# CM6206.net
KiCad netlist of a schematic drawn in Altium Designer
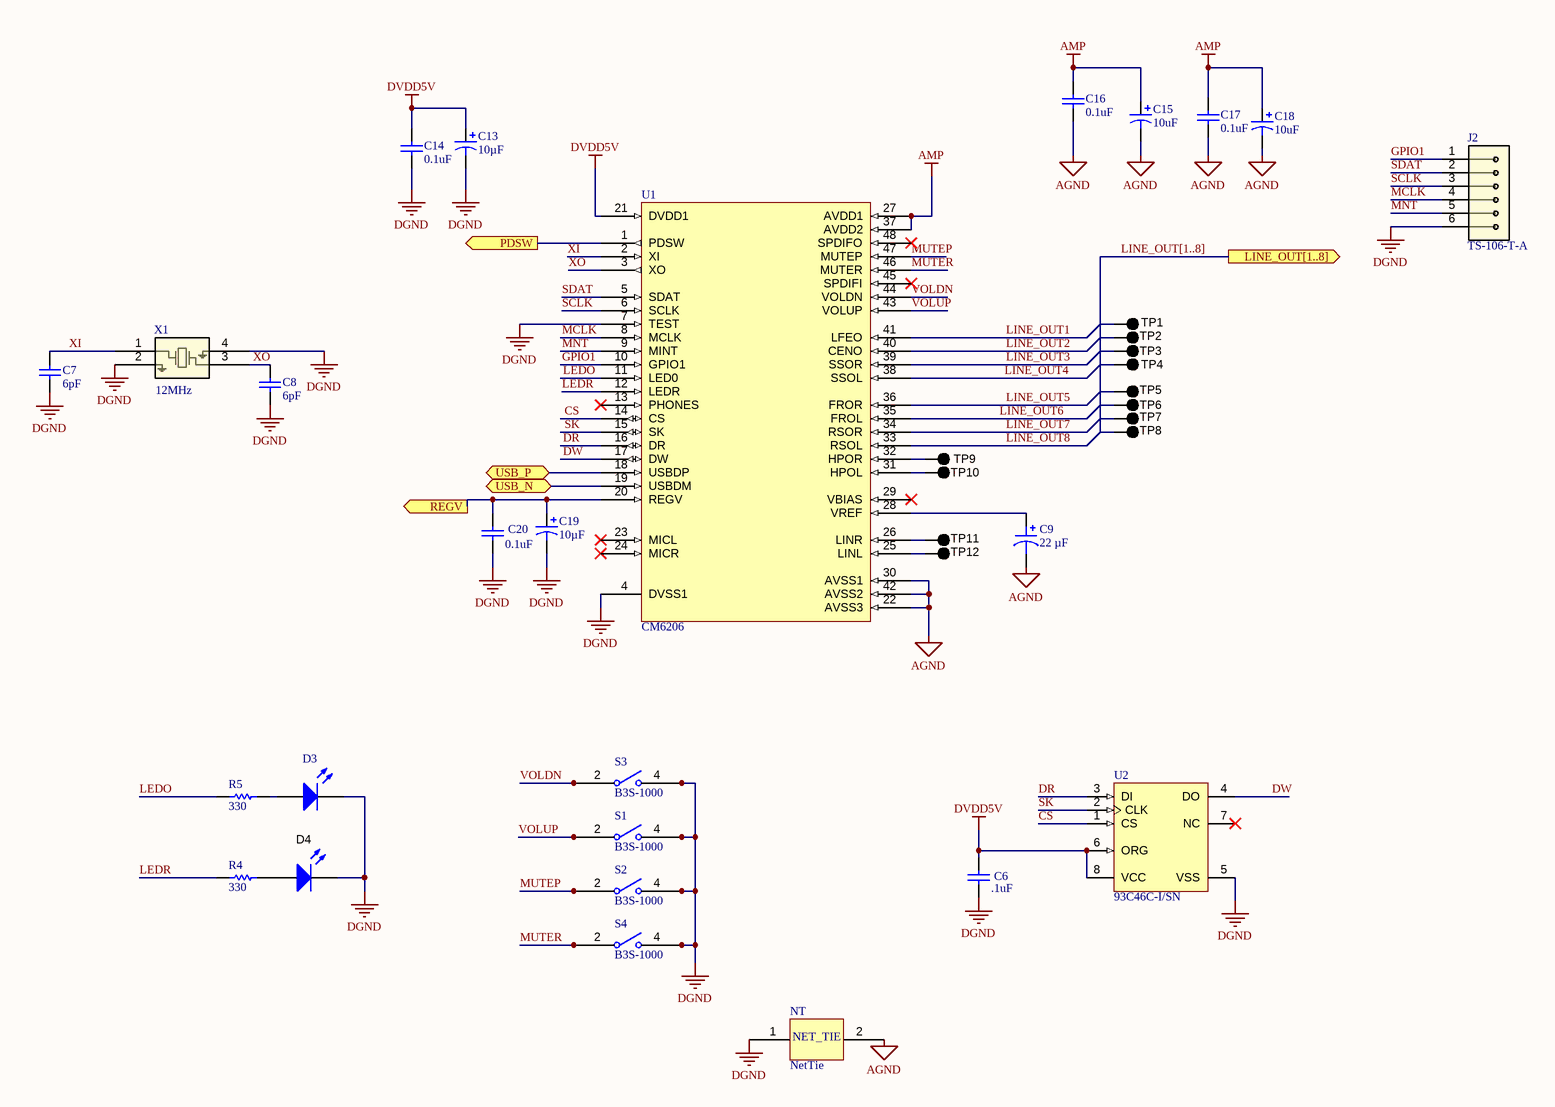
[diagram p0: CM6206.SchDoc]

(export (version "E")
  (design (tool "Eeschema 10.0.6"))
  (components
    (comp (ref "C6") (value ".1uF") (footprint "0603") (libsource (lib "SamlibSCH") (part "C TBD 0603")))
    (comp (ref "C7") (value "6pF") (footprint "0603") (libsource (lib "SamlibSCH") (part "C TBD 0603")))
    (comp (ref "C8") (value "6pF") (footprint "0603") (libsource (lib "SamlibSCH") (part "C TBD 0603")))
    (comp (ref "C9")
      (value "22 µF")
      (footprint "CAP POL 1411_3528")
      (description "CAP TANT 22UF 10% 10V 1411")
      (fields (field (name "PART NUMBER") "T495B226K010ATE500") (field (name "MANUFACTURER") "KEMET"))
      (libsource (lib "Celestial Altium Library - altium_library") (part "Polarised Capacitor"))
    )
    (comp (ref "C13")
      (value "10µF")
      (footprint "1206 TANT CASE A")
      (description "CAP TANT 10UF 16V 20% 1206")
      (fields (field (name "TOLERANCE") "±20%") (field (name "MANUFACTURER") "Kemet"))
      (libsource (lib "SamlibSCH") (part "T491A106M016AT"))
    )
    (comp (ref "C14") (value "0.1uF") (footprint "0603") (libsource (lib "SamlibSCH") (part "C TBD 0603")))
    (comp (ref "C15")
      (value "10uF")
      (footprint "1206 TANT CASE A")
      (description "CAP TANT 10UF 16V 20% 1206")
      (fields (field (name "TOLERANCE") "±20%") (field (name "MANUFACTURER") "Kemet"))
      (libsource (lib "SamlibSCH") (part "T491A106M016AT"))
    )
    (comp (ref "C16") (value "0.1uF") (footprint "0603") (libsource (lib "SamlibSCH") (part "C TBD 0603")))
    (comp (ref "C17") (value "0.1uF") (footprint "0603") (libsource (lib "SamlibSCH") (part "C TBD 0603")))
    (comp (ref "C18")
      (value "10uF")
      (footprint "1206 TANT CASE A")
      (description "CAP TANT 10UF 16V 20% 1206")
      (fields (field (name "TOLERANCE") "±20%") (field (name "MANUFACTURER") "Kemet"))
      (libsource (lib "SamlibSCH") (part "T491A106M016AT"))
    )
    (comp (ref "C19")
      (value "10µF")
      (footprint "1206 TANT CASE A")
      (description "CAP TANT 10UF 16V 20% 1206")
      (fields (field (name "TOLERANCE") "±20%") (field (name "MANUFACTURER") "Kemet"))
      (libsource (lib "SamlibSCH") (part "T491A106M016AT"))
    )
    (comp (ref "C20") (value "0.1uF") (footprint "0603") (libsource (lib "SamlibSCH") (part "C TBD 0603")))
    (comp (ref "D3")
      (value "LTST-C190KGKT")
      (footprint "LED_LTST-C190")
      (description "LED GREEN CLEAR 0603 SMD")
      (fields (field (name "MANUFACTURER") "Lite-On Inc."))
      (libsource (lib "SamlibSCH") (part "LTST-C190KGKT"))
    )
    (comp (ref "D4")
      (value "LB Q39G-L2OO-35-1")
      (footprint "LB Q39G_BLUE")
      (description "LED BLUE DIFFUSED 0603 SMD")
      (fields
        (field (name "MANUFACTURER") "OSRAM")
        (field (name "PARTNUMBER") "LB Q39G-L2N2-35-1")
        (field (name "PUBLISHER") "Texas Instruments")
      )
      (libsource (lib "SamlibSCH") (part "LB Q39G-L2N2-35-1"))
    )
    (comp (ref "J2")
      (value "TS-106-T-A")
      (footprint "CON6_1X6_TU_HTS_SAI")
      (description "No Description Available")
      (libsource (lib "Schlib1") (part "TS-106-T-A"))
    )
    (comp (ref "NT")
      (value "NetTie")
      (footprint "NetTie")
      (description "NET_TIE FOR EDGE")
      (libsource (lib "SamlibSCH") (part "NetTie"))
    )
    (comp (ref "R4") (value "330") (footprint "0603") (libsource (lib "SamlibSCH") (part "R TBD 0603")))
    (comp (ref "R5") (value "330") (footprint "0603") (libsource (lib "SamlibSCH") (part "R TBD 0603")))
    (comp (ref "S1")
      (value "B3S-1000")
      (footprint "B3S-1000_OMR")
      (libsource (lib "SamlibSCH") (part "B3S-1000"))
    )
    (comp (ref "S2")
      (value "B3S-1000")
      (footprint "B3S-1000_OMR")
      (libsource (lib "SamlibSCH") (part "B3S-1000"))
    )
    (comp (ref "S3")
      (value "B3S-1000")
      (footprint "B3S-1000_OMR")
      (libsource (lib "SamlibSCH") (part "B3S-1000"))
    )
    (comp (ref "S4")
      (value "B3S-1000")
      (footprint "B3S-1000_OMR")
      (libsource (lib "SamlibSCH") (part "B3S-1000"))
    )
    (comp (ref "TP1")
      (value "5001")
      (footprint "Testpoint pad")
      (description "TEST POINT PC MINI .040\"D BLACK")
      (fields (field (name "MANUFACTURER") "Keystone Electronics"))
      (libsource (lib "SamlibSCH") (part "5001"))
    )
    (comp (ref "TP2")
      (value "5001")
      (footprint "Testpoint pad")
      (description "TEST POINT PC MINI .040\"D BLACK")
      (fields (field (name "MANUFACTURER") "Keystone Electronics"))
      (libsource (lib "SamlibSCH") (part "5001"))
    )
    (comp (ref "TP3")
      (value "5001")
      (footprint "Testpoint pad")
      (description "TEST POINT PC MINI .040\"D BLACK")
      (fields (field (name "MANUFACTURER") "Keystone Electronics"))
      (libsource (lib "SamlibSCH") (part "5001"))
    )
    (comp (ref "TP4")
      (value "5001")
      (footprint "Testpoint pad")
      (description "TEST POINT PC MINI .040\"D BLACK")
      (fields (field (name "MANUFACTURER") "Keystone Electronics"))
      (libsource (lib "SamlibSCH") (part "5001"))
    )
    (comp (ref "TP5")
      (value "5001")
      (footprint "Testpoint pad")
      (description "TEST POINT PC MINI .040\"D BLACK")
      (fields (field (name "MANUFACTURER") "Keystone Electronics"))
      (libsource (lib "SamlibSCH") (part "5001"))
    )
    (comp (ref "TP6")
      (value "5001")
      (footprint "Testpoint pad")
      (description "TEST POINT PC MINI .040\"D BLACK")
      (fields (field (name "MANUFACTURER") "Keystone Electronics"))
      (libsource (lib "SamlibSCH") (part "5001"))
    )
    (comp (ref "TP7")
      (value "5001")
      (footprint "Testpoint pad")
      (description "TEST POINT PC MINI .040\"D BLACK")
      (fields (field (name "MANUFACTURER") "Keystone Electronics"))
      (libsource (lib "SamlibSCH") (part "5001"))
    )
    (comp (ref "TP8")
      (value "5001")
      (footprint "Testpoint pad")
      (description "TEST POINT PC MINI .040\"D BLACK")
      (fields (field (name "MANUFACTURER") "Keystone Electronics"))
      (libsource (lib "SamlibSCH") (part "5001"))
    )
    (comp (ref "TP9")
      (value "5001")
      (footprint "Testpoint pad")
      (description "TEST POINT PC MINI .040\"D BLACK")
      (fields (field (name "MANUFACTURER") "Keystone Electronics"))
      (libsource (lib "SamlibSCH") (part "5001"))
    )
    (comp (ref "TP10")
      (value "5001")
      (footprint "Testpoint pad")
      (description "TEST POINT PC MINI .040\"D BLACK")
      (fields (field (name "MANUFACTURER") "Keystone Electronics"))
      (libsource (lib "SamlibSCH") (part "5001"))
    )
    (comp (ref "TP11")
      (value "5001")
      (footprint "Testpoint pad")
      (description "TEST POINT PC MINI .040\"D BLACK")
      (fields (field (name "MANUFACTURER") "Keystone Electronics"))
      (libsource (lib "SamlibSCH") (part "5001"))
    )
    (comp (ref "TP12")
      (value "5001")
      (footprint "Testpoint pad")
      (description "TEST POINT PC MINI .040\"D BLACK")
      (fields (field (name "MANUFACTURER") "Keystone Electronics"))
      (libsource (lib "SamlibSCH") (part "5001"))
    )
    (comp (ref "U1") (value "CM6206") (footprint "CM6206 LQFP48") (libsource (lib "Schlib1") (part "CM6206")))
    (comp (ref "U2")
      (value "93C46C-I/SN")
      (footprint "SOIC-SN8_N")
      (description "1K, 128x8 or 64x16-bit, 5.0V Microwire Serial EEPROM, 8-Pin SOIC 150mil, Industrial Temperature")
      (libsource (lib "Altium Content Vault") (part "MEM-SEEPROM-93AA46C-P-8"))
    )
    (comp (ref "X1")
      (value "ECS-120-8-36-CKM-TR3")
      (footprint "ECS-120-8_ECS")
      (description "No Description Available")
      (libsource (lib "Schlib1") (part "ECS-120-8-36-CKM-TR3"))
    )
  )
  (nets
    (net (code "1") (name "/CS") (class "Default")
      (node (ref "U1") (pin "14") (pinfunction "CS_14") (pintype "bidirectional"))
      (node (ref "U2") (pin "1") (pinfunction "CS_1") (pintype "input"))
    )
    (net (code "2") (name "/DR") (class "Default")
      (node (ref "U1") (pin "16") (pinfunction "DR_16") (pintype "bidirectional"))
      (node (ref "U2") (pin "3") (pinfunction "DI_3") (pintype "input"))
    )
    (net (code "3") (name "/DW") (class "Default")
      (node (ref "U1") (pin "17") (pinfunction "DW_17") (pintype "bidirectional"))
      (node (ref "U2") (pin "4") (pinfunction "DO_4") (pintype "tri_state"))
    )
    (net (code "4") (name "/GPIO1") (class "Default")
      (node (ref "J2") (pin "1") (pinfunction "1_1") (pintype "passive"))
      (node (ref "U1") (pin "10") (pinfunction "GPIO1_10") (pintype "input"))
    )
    (net (code "5") (name "/LEDO") (class "Default")
      (node (ref "R5") (pin "2") (pinfunction "2_2") (pintype "passive"))
      (node (ref "U1") (pin "11") (pinfunction "LED0_11") (pintype "input"))
    )
    (net (code "6") (name "/LEDR") (class "Default")
      (node (ref "R4") (pin "2") (pinfunction "2_2") (pintype "passive"))
      (node (ref "U1") (pin "12") (pinfunction "LEDR_12") (pintype "input"))
    )
    (net (code "7") (name "/LINE_OUT1") (class "Default")
      (node (ref "TP1") (pin "1") (pintype "passive"))
      (node (ref "U1") (pin "41") (pinfunction "LFEO_41") (pintype "input"))
    )
    (net (code "8") (name "/LINE_OUT2") (class "Default")
      (node (ref "TP2") (pin "1") (pintype "passive"))
      (node (ref "U1") (pin "40") (pinfunction "CENO_40") (pintype "input"))
    )
    (net (code "9") (name "/LINE_OUT3") (class "Default")
      (node (ref "TP3") (pin "1") (pintype "passive"))
      (node (ref "U1") (pin "39") (pinfunction "SSOR_39") (pintype "input"))
    )
    (net (code "10") (name "/LINE_OUT4") (class "Default")
      (node (ref "TP4") (pin "1") (pintype "passive"))
      (node (ref "U1") (pin "38") (pinfunction "SSOL_38") (pintype "input"))
    )
    (net (code "11") (name "/LINE_OUT5") (class "Default")
      (node (ref "TP5") (pin "1") (pintype "passive"))
      (node (ref "U1") (pin "36") (pinfunction "FROR_36") (pintype "input"))
    )
    (net (code "12") (name "/LINE_OUT6") (class "Default")
      (node (ref "TP6") (pin "1") (pintype "passive"))
      (node (ref "U1") (pin "35") (pinfunction "FROL_35") (pintype "input"))
    )
    (net (code "13") (name "/LINE_OUT7") (class "Default")
      (node (ref "TP7") (pin "1") (pintype "passive"))
      (node (ref "U1") (pin "34") (pinfunction "RSOR_34") (pintype "input"))
    )
    (net (code "14") (name "/LINE_OUT8") (class "Default")
      (node (ref "TP8") (pin "1") (pintype "passive"))
      (node (ref "U1") (pin "33") (pinfunction "RSOL_33") (pintype "input"))
    )
    (net (code "16") (name "/MCLK") (class "Default")
      (node (ref "J2") (pin "4") (pinfunction "4_4") (pintype "passive"))
      (node (ref "U1") (pin "8") (pinfunction "MCLK_8") (pintype "input"))
    )
    (net (code "17") (name "/MNT") (class "Default")
      (node (ref "J2") (pin "5") (pinfunction "5_5") (pintype "passive"))
      (node (ref "U1") (pin "9") (pinfunction "MINT_9") (pintype "input"))
    )
    (net (code "18") (name "/MUTEP") (class "Default")
      (node (ref "S2") (pin "1") (pinfunction "1_1") (pintype "passive"))
      (node (ref "S2") (pin "2") (pinfunction "2_2") (pintype "passive"))
      (node (ref "U1") (pin "47") (pinfunction "MUTEP_47") (pintype "input"))
    )
    (net (code "19") (name "/MUTER") (class "Default")
      (node (ref "S4") (pin "1") (pinfunction "1_1") (pintype "passive"))
      (node (ref "S4") (pin "2") (pinfunction "2_2") (pintype "passive"))
      (node (ref "U1") (pin "46") (pinfunction "MUTER_46") (pintype "input"))
    )
    (net (code "20") (name "/PDSW") (class "Default")
      (node (ref "U1") (pin "1") (pinfunction "PDSW_1") (pintype "output"))
    )
    (net (code "21") (name "/REGV") (class "Default")
      (node (ref "C19") (pin "2") (pinfunction "2_2") (pintype "passive"))
      (node (ref "C20") (pin "2") (pinfunction "2_2") (pintype "passive"))
      (node (ref "U1") (pin "20") (pinfunction "REGV_20") (pintype "input"))
    )
    (net (code "22") (name "/SCLK") (class "Default")
      (node (ref "J2") (pin "3") (pinfunction "3_3") (pintype "passive"))
      (node (ref "U1") (pin "6") (pinfunction "SCLK_6") (pintype "input"))
    )
    (net (code "23") (name "/SDAT") (class "Default")
      (node (ref "J2") (pin "2") (pinfunction "2_2") (pintype "passive"))
      (node (ref "U1") (pin "5") (pinfunction "SDAT_5") (pintype "input"))
    )
    (net (code "24") (name "/SK") (class "Default")
      (node (ref "U1") (pin "15") (pinfunction "SK_15") (pintype "bidirectional"))
      (node (ref "U2") (pin "2") (pinfunction "CLK_2") (pintype "input"))
    )
    (net (code "25") (name "/USB_N") (class "Default")
      (node (ref "U1") (pin "19") (pinfunction "USBDM_19") (pintype "input"))
    )
    (net (code "26") (name "/USB_P") (class "Default")
      (node (ref "U1") (pin "18") (pinfunction "USBDP_18") (pintype "input"))
    )
    (net (code "27") (name "/VOLDN") (class "Default")
      (node (ref "S3") (pin "1") (pinfunction "1_1") (pintype "passive"))
      (node (ref "S3") (pin "2") (pinfunction "2_2") (pintype "passive"))
      (node (ref "U1") (pin "44") (pinfunction "VOLDN_44") (pintype "input"))
    )
    (net (code "28") (name "/VOLUP") (class "Default")
      (node (ref "S1") (pin "1") (pinfunction "1_1") (pintype "passive"))
      (node (ref "S1") (pin "2") (pinfunction "2_2") (pintype "passive"))
      (node (ref "U1") (pin "43") (pinfunction "VOLUP_43") (pintype "input"))
    )
    (net (code "29") (name "/XI") (class "Default")
      (node (ref "C7") (pin "2") (pinfunction "2_2") (pintype "passive"))
      (node (ref "U1") (pin "2") (pinfunction "XI_2") (pintype "input"))
      (node (ref "X1") (pin "1") (pinfunction "1_1") (pintype "passive"))
    )
    (net (code "30") (name "/XO") (class "Default")
      (node (ref "C8") (pin "2") (pinfunction "2_2") (pintype "passive"))
      (node (ref "U1") (pin "3") (pinfunction "XO_3") (pintype "output"))
      (node (ref "X1") (pin "3") (pinfunction "3_3") (pintype "passive"))
    )
    (net (code "31") (name "AGND") (class "Default")
      (node (ref "C15") (pin "1") (pinfunction "1_1") (pintype "passive"))
      (node (ref "C16") (pin "1") (pinfunction "1_1") (pintype "passive"))
      (node (ref "C17") (pin "1") (pinfunction "1_1") (pintype "passive"))
      (node (ref "C18") (pin "1") (pinfunction "1_1") (pintype "passive"))
      (node (ref "C9") (pin "2") (pinfunction "2_2") (pintype "passive"))
      (node (ref "NT") (pin "2") (pinfunction "2_2") (pintype "passive"))
      (node (ref "U1") (pin "22") (pinfunction "AVSS3_22") (pintype "input"))
      (node (ref "U1") (pin "30") (pinfunction "AVSS1_30") (pintype "input"))
      (node (ref "U1") (pin "42") (pinfunction "AVSS2_42") (pintype "input"))
    )
    (net (code "32") (name "AMP") (class "Default")
      (node (ref "C15") (pin "2") (pinfunction "2_2") (pintype "passive"))
      (node (ref "C16") (pin "2") (pinfunction "2_2") (pintype "passive"))
      (node (ref "C17") (pin "2") (pinfunction "2_2") (pintype "passive"))
      (node (ref "C18") (pin "2") (pinfunction "2_2") (pintype "passive"))
      (node (ref "U1") (pin "27") (pinfunction "AVDD1_27") (pintype "input"))
      (node (ref "U1") (pin "37") (pinfunction "AVDD2_37") (pintype "input"))
    )
    (net (code "33") (name "DGND") (class "Default")
      (node (ref "C13") (pin "1") (pinfunction "1_1") (pintype "passive"))
      (node (ref "C14") (pin "1") (pinfunction "1_1") (pintype "passive"))
      (node (ref "C19") (pin "1") (pinfunction "1_1") (pintype "passive"))
      (node (ref "C20") (pin "1") (pinfunction "1_1") (pintype "passive"))
      (node (ref "C6") (pin "1") (pinfunction "1_1") (pintype "passive"))
      (node (ref "C7") (pin "1") (pinfunction "1_1") (pintype "passive"))
      (node (ref "C8") (pin "1") (pinfunction "1_1") (pintype "passive"))
      (node (ref "D3") (pin "2") (pinfunction "K_2") (pintype "passive"))
      (node (ref "D4") (pin "2") (pinfunction "K_2") (pintype "passive"))
      (node (ref "J2") (pin "6") (pinfunction "6_6") (pintype "passive"))
      (node (ref "NT") (pin "1") (pinfunction "1_1") (pintype "passive"))
      (node (ref "S1") (pin "3") (pinfunction "3_3") (pintype "passive"))
      (node (ref "S1") (pin "4") (pinfunction "4_4") (pintype "passive"))
      (node (ref "S2") (pin "3") (pinfunction "3_3") (pintype "passive"))
      (node (ref "S2") (pin "4") (pinfunction "4_4") (pintype "passive"))
      (node (ref "S3") (pin "3") (pinfunction "3_3") (pintype "passive"))
      (node (ref "S3") (pin "4") (pinfunction "4_4") (pintype "passive"))
      (node (ref "S4") (pin "3") (pinfunction "3_3") (pintype "passive"))
      (node (ref "S4") (pin "4") (pinfunction "4_4") (pintype "passive"))
      (node (ref "U1") (pin "4") (pinfunction "DVSS1_4") (pintype "power_in"))
      (node (ref "U1") (pin "7") (pinfunction "TEST_7") (pintype "input"))
      (node (ref "U2") (pin "5") (pinfunction "VSS_5") (pintype "power_in"))
      (node (ref "X1") (pin "2") (pinfunction "2_2") (pintype "passive"))
      (node (ref "X1") (pin "4") (pinfunction "4_4") (pintype "passive"))
    )
    (net (code "34") (name "DVDD5V") (class "Default")
      (node (ref "C13") (pin "2") (pinfunction "2_2") (pintype "passive"))
      (node (ref "C14") (pin "2") (pinfunction "2_2") (pintype "passive"))
      (node (ref "C6") (pin "2") (pinfunction "2_2") (pintype "passive"))
      (node (ref "U1") (pin "21") (pinfunction "DVDD1_21") (pintype "input"))
      (node (ref "U2") (pin "6") (pinfunction "ORG_6") (pintype "input"))
      (node (ref "U2") (pin "8") (pinfunction "VCC_8") (pintype "power_in"))
    )
    (net (code "35") (name "Net-(D3-A)") (class "Default")
      (node (ref "D3") (pin "1") (pinfunction "A_1") (pintype "passive"))
      (node (ref "R5") (pin "1") (pinfunction "1_1") (pintype "passive"))
    )
    (net (code "36") (name "Net-(D4-A)") (class "Default")
      (node (ref "D4") (pin "1") (pinfunction "A_1") (pintype "passive"))
      (node (ref "R4") (pin "1") (pinfunction "1_1") (pintype "passive"))
    )
    (net (code "37") (name "Net-(U1-HPOL)") (class "Default")
      (node (ref "TP10") (pin "1") (pintype "passive"))
      (node (ref "U1") (pin "31") (pinfunction "HPOL_31") (pintype "input"))
    )
    (net (code "38") (name "Net-(U1-HPOR)") (class "Default")
      (node (ref "TP9") (pin "1") (pintype "passive"))
      (node (ref "U1") (pin "32") (pinfunction "HPOR_32") (pintype "input"))
    )
    (net (code "39") (name "Net-(U1-LINL)") (class "Default")
      (node (ref "TP12") (pin "1") (pintype "passive"))
      (node (ref "U1") (pin "25") (pinfunction "LINL_25") (pintype "input"))
    )
    (net (code "40") (name "Net-(U1-LINR)") (class "Default")
      (node (ref "TP11") (pin "1") (pintype "passive"))
      (node (ref "U1") (pin "26") (pinfunction "LINR_26") (pintype "input"))
    )
    (net (code "41") (name "Net-(U1-VREF)") (class "Default")
      (node (ref "C9") (pin "1") (pinfunction "1_1") (pintype "passive"))
      (node (ref "U1") (pin "28") (pinfunction "VREF_28") (pintype "input"))
    )
    (net (code "42") (name "unconnected-(U1-MICL-Pad23)") (class "Default")
      (node (ref "U1") (pin "23") (pinfunction "MICL_23") (pintype "input+no_connect"))
    )
    (net (code "43") (name "unconnected-(U1-MICR-Pad24)") (class "Default")
      (node (ref "U1") (pin "24") (pinfunction "MICR_24") (pintype "input+no_connect"))
    )
    (net (code "44") (name "unconnected-(U1-PHONES-Pad13)") (class "Default")
      (node (ref "U1") (pin "13") (pinfunction "PHONES_13") (pintype "input+no_connect"))
    )
    (net (code "45") (name "unconnected-(U1-SPDIFI-Pad45)") (class "Default")
      (node (ref "U1") (pin "45") (pinfunction "SPDIFI_45") (pintype "input+no_connect"))
    )
    (net (code "46") (name "unconnected-(U1-SPDIFO-Pad48)") (class "Default")
      (node (ref "U1") (pin "48") (pinfunction "SPDIFO_48") (pintype "input+no_connect"))
    )
    (net (code "47") (name "unconnected-(U1-VBIAS-Pad29)") (class "Default")
      (node (ref "U1") (pin "29") (pinfunction "VBIAS_29") (pintype "input+no_connect"))
    )
    (net (code "48") (name "unconnected-(U2-NC-Pad7)") (class "Default")
      (node (ref "U2") (pin "7") (pinfunction "NC_7") (pintype "passive+no_connect"))
    )
  )
)
